# SINTETIZADOR_Y_DDS_SLAVE.net
KiCad netlist of a schematic drawn in Altium Designer
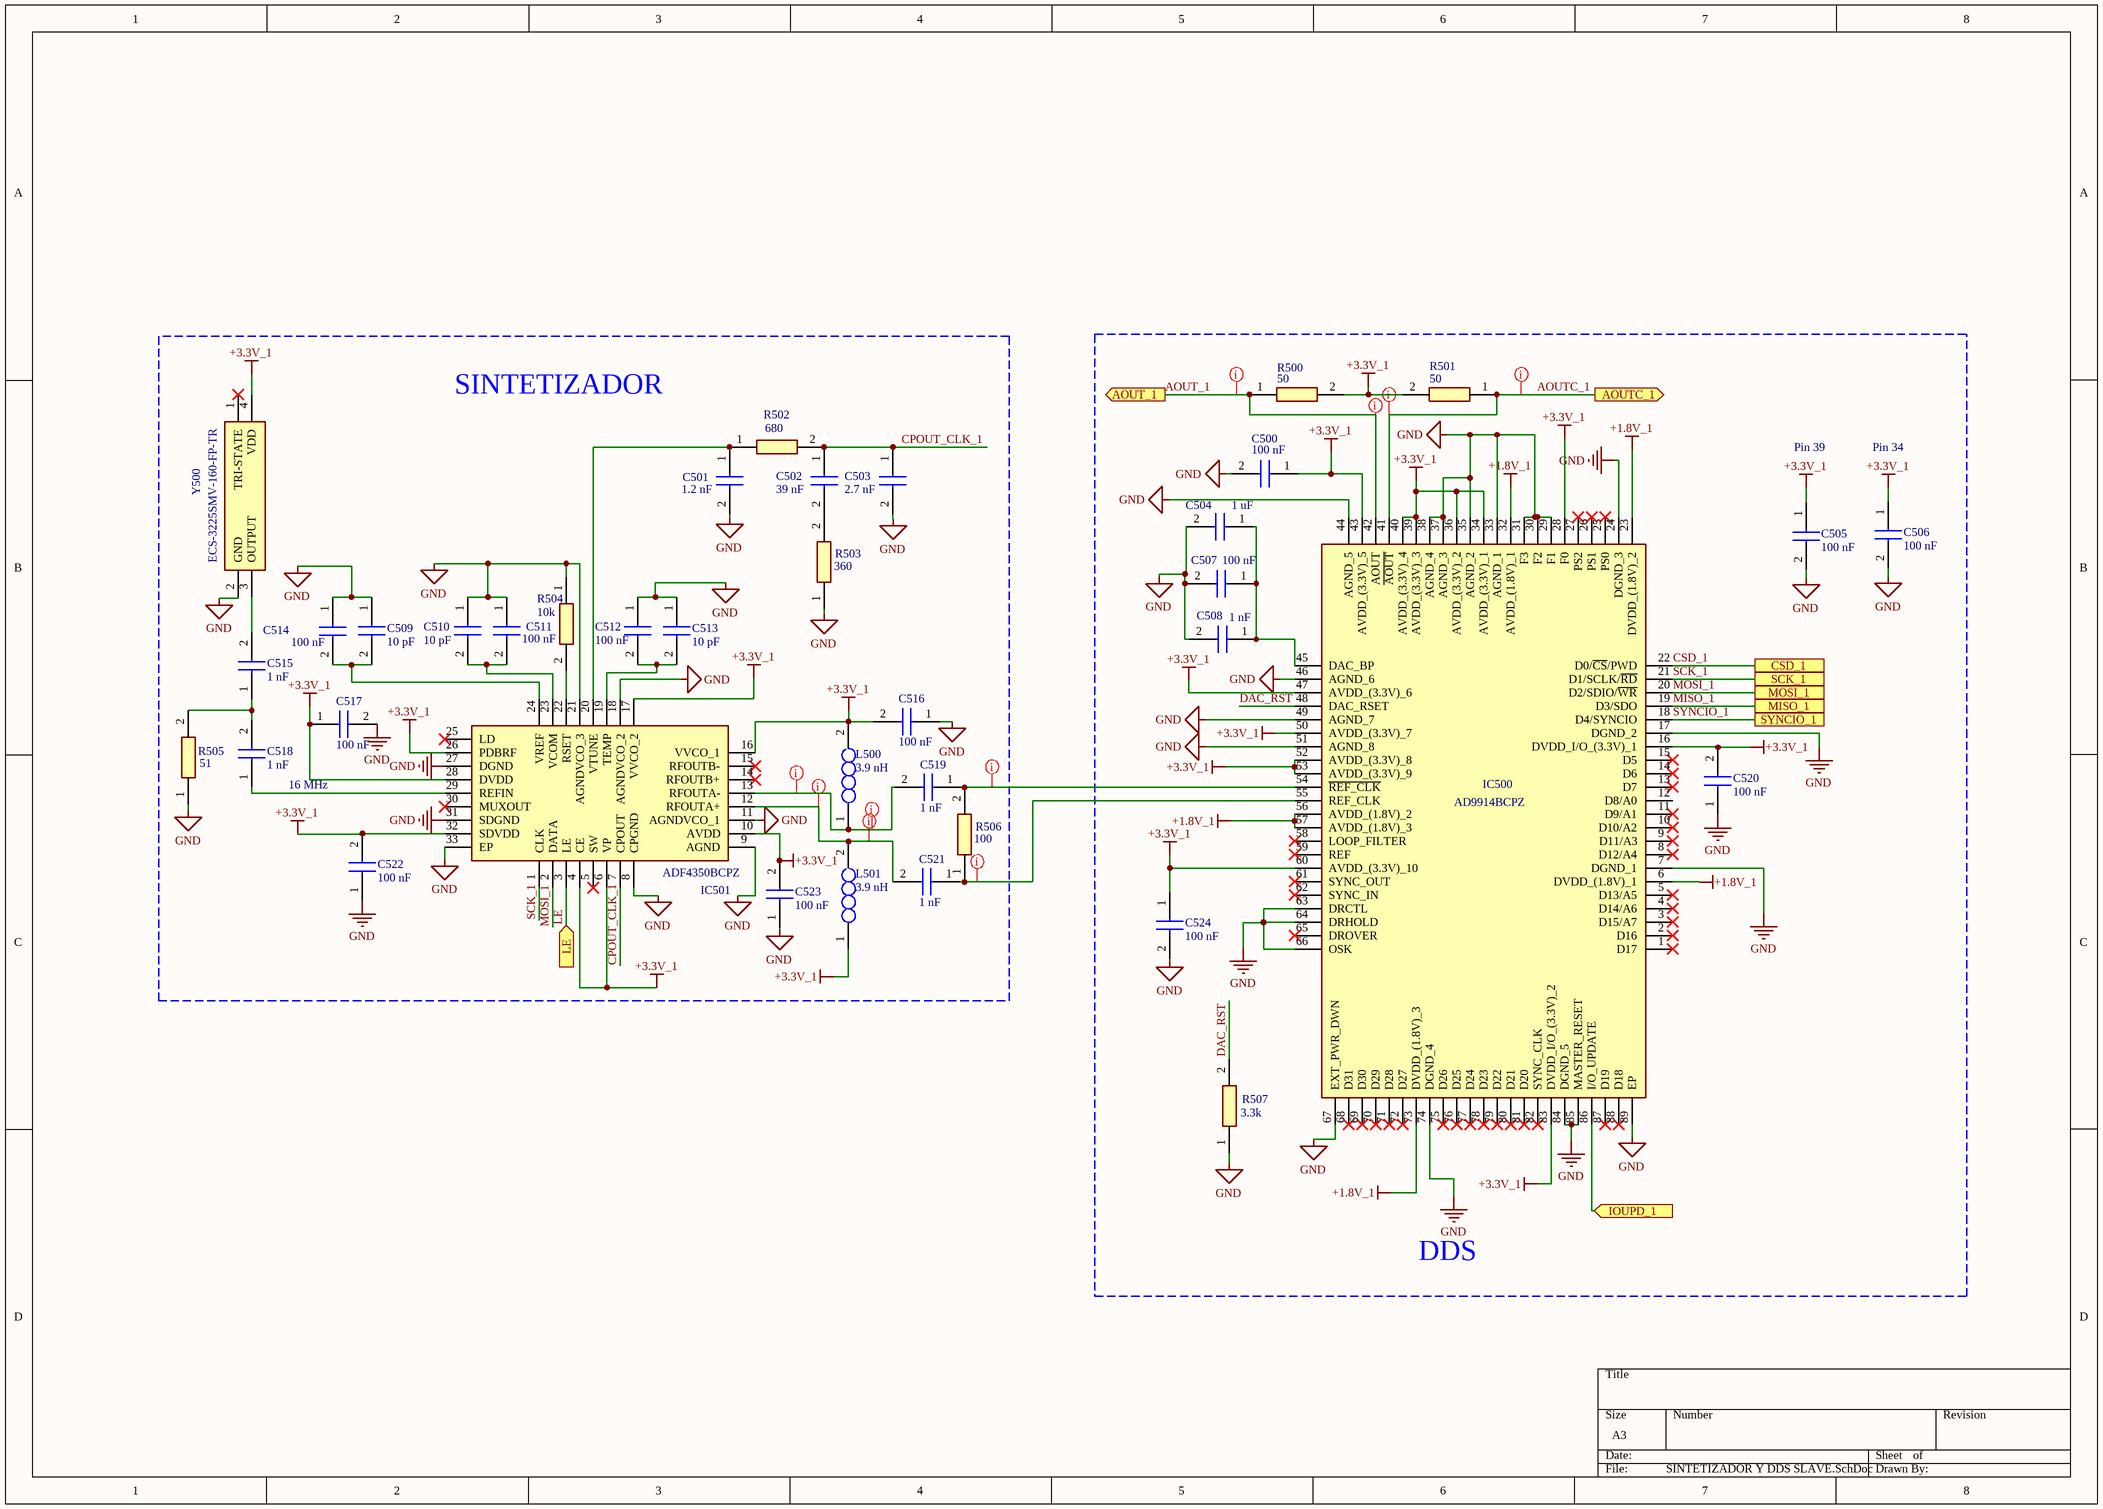
[diagram p0: SINTETIZADOR Y DDS SLAVE.SchDoc]

(export (version "E")
  (design (tool "Eeschema 10.0.6"))
  (components
    (comp (ref "C500")
      (value "100 nF")
      (footprint "SamacSys:C0603")
      (description "Capacitor")
      (fields (field (name "MANUFACTURER_PART_NUMBER") "C0603H470J5GACTU"))
      (libsource (lib "LIBRERIA_GEN_V2.0") (part "C0603H470J5GACTU"))
    )
    (comp (ref "C501")
      (value "1.2 nF")
      (footprint "SamacSys:C0603")
      (description "Capacitor")
      (fields (field (name "MANUFACTURER_PART_NUMBER") "C0603H470J5GACTU"))
      (libsource (lib "LIBRERIA_GEN_V2.0") (part "C0603H470J5GACTU"))
    )
    (comp (ref "C502")
      (value "39 nF")
      (footprint "SamacSys:C0603")
      (description "Capacitor")
      (fields (field (name "MANUFACTURER_PART_NUMBER") "C0603H470J5GACTU"))
      (libsource (lib "LIBRERIA_GEN_V2.0") (part "C0603H470J5GACTU"))
    )
    (comp (ref "C503")
      (value "2.7 nF")
      (footprint "SamacSys:C0603")
      (description "Capacitor")
      (fields (field (name "MANUFACTURER_PART_NUMBER") "C0603H470J5GACTU"))
      (libsource (lib "LIBRERIA_GEN_V2.0") (part "C0603H470J5GACTU"))
    )
    (comp (ref "C504")
      (value "1 uF")
      (footprint "SamacSys:C0603")
      (description "Capacitor")
      (fields (field (name "MANUFACTURER_PART_NUMBER") "C0603H470J5GACTU"))
      (libsource (lib "LIBRERIA_GEN_V2.0") (part "C0603H470J5GACTU"))
    )
    (comp (ref "C505")
      (value "100 nF")
      (footprint "SamacSys:C0603")
      (description "Capacitor")
      (fields (field (name "MANUFACTURER_PART_NUMBER") "C0603H470J5GACTU"))
      (libsource (lib "LIBRERIA_GEN_V2.0") (part "C0603H470J5GACTU"))
    )
    (comp (ref "C506")
      (value "100 nF")
      (footprint "SamacSys:C0603")
      (description "Capacitor")
      (fields (field (name "MANUFACTURER_PART_NUMBER") "C0603H470J5GACTU"))
      (libsource (lib "LIBRERIA_GEN_V2.0") (part "C0603H470J5GACTU"))
    )
    (comp (ref "C507")
      (value "100 nF")
      (footprint "SamacSys:C0603")
      (description "Capacitor")
      (fields (field (name "MANUFACTURER_PART_NUMBER") "C0603H470J5GACTU"))
      (libsource (lib "LIBRERIA_GEN_V2.0") (part "C0603H470J5GACTU"))
    )
    (comp (ref "C508")
      (value "1 nF")
      (footprint "SamacSys:C0603")
      (description "Capacitor")
      (fields (field (name "MANUFACTURER_PART_NUMBER") "C0603H470J5GACTU"))
      (libsource (lib "LIBRERIA_GEN_V2.0") (part "C0603H470J5GACTU"))
    )
    (comp (ref "C509")
      (value "10 pF")
      (footprint "SamacSys:C0603")
      (description "Capacitor")
      (fields (field (name "MANUFACTURER_PART_NUMBER") "C0603H470J5GACTU"))
      (libsource (lib "LIBRERIA_GEN_V2.0") (part "C0603H470J5GACTU"))
    )
    (comp (ref "C510")
      (value "10 pF")
      (footprint "SamacSys:C0603")
      (description "Capacitor")
      (fields (field (name "MANUFACTURER_PART_NUMBER") "C0603H470J5GACTU"))
      (libsource (lib "LIBRERIA_GEN_V2.0") (part "C0603H470J5GACTU"))
    )
    (comp (ref "C511")
      (value "100 nF")
      (footprint "SamacSys:C0603")
      (description "Capacitor")
      (fields (field (name "MANUFACTURER_PART_NUMBER") "C0603H470J5GACTU"))
      (libsource (lib "LIBRERIA_GEN_V2.0") (part "C0603H470J5GACTU"))
    )
    (comp (ref "C512")
      (value "100 nF")
      (footprint "SamacSys:C0603")
      (description "Capacitor")
      (fields (field (name "MANUFACTURER_PART_NUMBER") "C0603H470J5GACTU"))
      (libsource (lib "LIBRERIA_GEN_V2.0") (part "C0603H470J5GACTU"))
    )
    (comp (ref "C513")
      (value "10 pF")
      (footprint "SamacSys:C0603")
      (description "Capacitor")
      (fields (field (name "MANUFACTURER_PART_NUMBER") "C0603H470J5GACTU"))
      (libsource (lib "LIBRERIA_GEN_V2.0") (part "C0603H470J5GACTU"))
    )
    (comp (ref "C514")
      (value "100 nF")
      (footprint "SamacSys:C0603")
      (description "Capacitor")
      (fields (field (name "MANUFACTURER_PART_NUMBER") "C0603H470J5GACTU"))
      (libsource (lib "LIBRERIA_GEN_V2.0") (part "C0603H470J5GACTU"))
    )
    (comp (ref "C515")
      (value "1 nF")
      (footprint "SamacSys:C0603")
      (description "Capacitor")
      (fields (field (name "MANUFACTURER_PART_NUMBER") "C0603H470J5GACTU"))
      (libsource (lib "LIBRERIA_GEN_V2.0") (part "C0603H470J5GACTU"))
    )
    (comp (ref "C516")
      (value "100 nF")
      (footprint "SamacSys:C0603")
      (description "Capacitor")
      (fields (field (name "MANUFACTURER_PART_NUMBER") "C0603H470J5GACTU"))
      (libsource (lib "LIBRERIA_GEN_V2.0") (part "C0603H470J5GACTU"))
    )
    (comp (ref "C517")
      (value "100 nF")
      (footprint "SamacSys:C0603")
      (description "Capacitor")
      (fields (field (name "MANUFACTURER_PART_NUMBER") "C0603H470J5GACTU"))
      (libsource (lib "LIBRERIA_GEN_V2.0") (part "C0603H470J5GACTU"))
    )
    (comp (ref "C518")
      (value "1 nF")
      (footprint "SamacSys:C0603")
      (description "Capacitor")
      (fields (field (name "MANUFACTURER_PART_NUMBER") "C0603H470J5GACTU"))
      (libsource (lib "LIBRERIA_GEN_V2.0") (part "C0603H470J5GACTU"))
    )
    (comp (ref "C519")
      (value "1 nF")
      (footprint "SamacSys:C0603")
      (description "Capacitor")
      (fields (field (name "MANUFACTURER_PART_NUMBER") "C0603H470J5GACTU"))
      (libsource (lib "LIBRERIA_GEN_V2.0") (part "C0603H470J5GACTU"))
    )
    (comp (ref "C520")
      (value "100 nF")
      (footprint "SamacSys:C0603")
      (description "Capacitor")
      (fields (field (name "MANUFACTURER_PART_NUMBER") "C0603H470J5GACTU"))
      (libsource (lib "LIBRERIA_GEN_V2.0") (part "C0603H470J5GACTU"))
    )
    (comp (ref "C521")
      (value "1 nF")
      (footprint "SamacSys:C0603")
      (description "Capacitor")
      (fields (field (name "MANUFACTURER_PART_NUMBER") "C0603H470J5GACTU"))
      (libsource (lib "LIBRERIA_GEN_V2.0") (part "C0603H470J5GACTU"))
    )
    (comp (ref "C522")
      (value "100 nF")
      (footprint "SamacSys:C0603")
      (description "Capacitor")
      (fields (field (name "MANUFACTURER_PART_NUMBER") "C0603H470J5GACTU"))
      (libsource (lib "LIBRERIA_GEN_V2.0") (part "C0603H470J5GACTU"))
    )
    (comp (ref "C523")
      (value "100 nF")
      (footprint "SamacSys:C0603")
      (description "Capacitor")
      (fields (field (name "MANUFACTURER_PART_NUMBER") "C0603H470J5GACTU"))
      (libsource (lib "LIBRERIA_GEN_V2.0") (part "C0603H470J5GACTU"))
    )
    (comp (ref "C524")
      (value "100 nF")
      (footprint "SamacSys:C0603")
      (description "Capacitor")
      (fields (field (name "MANUFACTURER_PART_NUMBER") "C0603H470J5GACTU"))
      (libsource (lib "LIBRERIA_GEN_V2.0") (part "C0603H470J5GACTU"))
    )
    (comp (ref "IC500")
      (value "AD9914BCPZ")
      (footprint "SamacSys:QFN50P1200X1200X90-89N-D")
      (description "Integrated Circuit")
      (fields (field (name "MOUSER PART NUMBER") "584-AD9914BCPZ"))
      (libsource (lib "LIBRERIA_GEN_V2.0") (part "AD9914BCPZ"))
    )
    (comp (ref "IC501")
      (value "ADF4350BCPZ")
      (footprint "SamacSys:QFN50P500X500X100-33N")
      (description "Integrated Circuit")
      (fields (field (name "MOUSER PART NUMBER") "584-ADF4350BCPZ"))
      (libsource (lib "LIBRERIA_GEN_V2.0") (part "ADF4350BCPZ"))
    )
    (comp (ref "L500")
      (value "3.9 nH")
      (footprint "SamacSys:INDC1608X95N")
      (description "Inductor")
      (fields
        (field (name "MANUFACTURER_PART_NUMBER") "AIML-0603-100K-T")
        (field (name "MOUSER PART NUMBER") "815-AIML-0603-100KT")
      )
      (libsource (lib "*") (part "AIML-0603-100K-T"))
    )
    (comp (ref "L501")
      (value "3.9 nH")
      (footprint "SamacSys:INDC1608X95N")
      (description "Inductor")
      (fields
        (field (name "MANUFACTURER_PART_NUMBER") "AIML-0603-100K-T")
        (field (name "MOUSER PART NUMBER") "815-AIML-0603-100KT")
      )
      (libsource (lib "*") (part "AIML-0603-100K-T"))
    )
    (comp (ref "R500")
      (value "50")
      (footprint "SamacSys:RESC1608X55N")
      (description "Resistor")
      (fields
        (field (name "MANUFACTURER_PART_NUMBER") "CR0603-FX-1431ELF")
        (field (name "MOUSER PART NUMBER") "652-CR0603FX-1431ELF")
      )
      (libsource (lib "") (part "CR0603-FX-1431ELF_1"))
    )
    (comp (ref "R501")
      (value "50")
      (footprint "SamacSys:RESC1608X55N")
      (description "Resistor")
      (fields
        (field (name "MANUFACTURER_PART_NUMBER") "CR0603-FX-1431ELF")
        (field (name "MOUSER PART NUMBER") "652-CR0603FX-1431ELF")
      )
      (libsource (lib "") (part "CR0603-FX-1431ELF_3"))
    )
    (comp (ref "R502")
      (value "680")
      (footprint "SamacSys:RESC1608X55N")
      (description "Resistor")
      (fields
        (field (name "MANUFACTURER_PART_NUMBER") "CR0603-FX-1431ELF")
        (field (name "MOUSER PART NUMBER") "652-CR0603FX-1431ELF")
      )
      (libsource (lib "") (part "CR0603-FX-1431ELF_1"))
    )
    (comp (ref "R503")
      (value "360")
      (footprint "SamacSys:RESC1608X55N")
      (description "Resistor")
      (fields
        (field (name "MANUFACTURER_PART_NUMBER") "CR0603-FX-1431ELF")
        (field (name "MOUSER PART NUMBER") "652-CR0603FX-1431ELF")
      )
      (libsource (lib "") (part "CR0603-FX-1431ELF_2"))
    )
    (comp (ref "R504")
      (value "10k")
      (footprint "SamacSys:RESC1608X55N")
      (description "Resistor")
      (fields
        (field (name "MANUFACTURER_PART_NUMBER") "CR0603-FX-1431ELF")
        (field (name "MOUSER PART NUMBER") "652-CR0603FX-1431ELF")
      )
      (libsource (lib "LIBRERIA_GEN_V2.0") (part "CR0603-FX-1431ELF"))
    )
    (comp (ref "R505")
      (value "51")
      (footprint "SamacSys:RESC1608X55N")
      (description "Resistor")
      (fields
        (field (name "MANUFACTURER_PART_NUMBER") "CR0603-FX-1431ELF")
        (field (name "MOUSER PART NUMBER") "652-CR0603FX-1431ELF")
      )
      (libsource (lib "") (part "CR0603-FX-1431ELF_2"))
    )
    (comp (ref "R506")
      (value "100")
      (footprint "SamacSys:RESC1608X55N")
      (description "Resistor")
      (fields
        (field (name "MANUFACTURER_PART_NUMBER") "CR0603-FX-1431ELF")
        (field (name "MOUSER PART NUMBER") "652-CR0603FX-1431ELF")
      )
      (libsource (lib "") (part "CR0603-FX-1431ELF_2"))
    )
    (comp (ref "R507")
      (value "3.3k")
      (footprint "SamacSys:RESC1608X55N")
      (description "Resistor")
      (fields
        (field (name "MANUFACTURER_PART_NUMBER") "CR0603-FX-1431ELF")
        (field (name "MOUSER PART NUMBER") "652-CR0603FX-1431ELF")
      )
      (libsource (lib "") (part "CR0603-FX-1431ELF_2"))
    )
    (comp (ref "Y500")
      (value "ECS-3225SMV-160-FP-TR")
      (footprint "SamacSys:ECS3225SMV160FPTR")
      (description "Crystal or Oscillator")
      (fields (field (name "MOUSER PART NUMBER") "520-3225SMV-160-FPT"))
      (libsource (lib "LIBRERIA_GEN_V2.0") (part "ECS-3225SMV-160-FP-TR"))
    )
  )
  (nets
    (net (code "1") (name "+1.8V_1") (class "Default")
      (node (ref "IC500") (pin "23") (pinfunction "DVDD_(1.8V)_2_23") (pintype "passive"))
      (node (ref "IC500") (pin "32") (pinfunction "AVDD_(1.8V)_1_32") (pintype "passive"))
      (node (ref "IC500") (pin "56") (pinfunction "AVDD_(1.8V)_2_56") (pintype "passive"))
      (node (ref "IC500") (pin "57") (pinfunction "AVDD_(1.8V)_3_57") (pintype "passive"))
      (node (ref "IC500") (pin "6") (pinfunction "DVDD_(1.8V)_1_6") (pintype "passive"))
      (node (ref "IC500") (pin "73") (pinfunction "DVDD_(1.8V)_3_73") (pintype "passive"))
    )
    (net (code "2") (name "+3.3V_1") (class "Default")
      (node (ref "C500") (pin "1") (pinfunction "1_1") (pintype "passive"))
      (node (ref "C505") (pin "1") (pinfunction "1_1") (pintype "passive"))
      (node (ref "C506") (pin "1") (pinfunction "1_1") (pintype "passive"))
      (node (ref "C516") (pin "2") (pinfunction "2_2") (pintype "passive"))
      (node (ref "C517") (pin "1") (pinfunction "1_1") (pintype "passive"))
      (node (ref "C520") (pin "2") (pinfunction "2_2") (pintype "passive"))
      (node (ref "C522") (pin "2") (pinfunction "2_2") (pintype "passive"))
      (node (ref "C523") (pin "2") (pinfunction "2_2") (pintype "passive"))
      (node (ref "C524") (pin "1") (pinfunction "1_1") (pintype "passive"))
      (node (ref "IC500") (pin "16") (pinfunction "DVDD_I/O_(3.3V)_1_16") (pintype "passive"))
      (node (ref "IC500") (pin "28") (pinfunction "F0_28") (pintype "passive"))
      (node (ref "IC500") (pin "34") (pinfunction "AVDD_(3.3V)_1_34") (pintype "passive"))
      (node (ref "IC500") (pin "36") (pinfunction "AVDD_(3.3V)_2_36") (pintype "passive"))
      (node (ref "IC500") (pin "39") (pinfunction "AVDD_(3.3V)_3_39") (pintype "passive"))
      (node (ref "IC500") (pin "40") (pinfunction "AVDD_(3.3V)_4_40") (pintype "passive"))
      (node (ref "IC500") (pin "43") (pinfunction "AVDD_(3.3V)_5_43") (pintype "passive"))
      (node (ref "IC500") (pin "47") (pinfunction "AVDD_(3.3V)_6_47") (pintype "passive"))
      (node (ref "IC500") (pin "50") (pinfunction "AVDD_(3.3V)_7_50") (pintype "passive"))
      (node (ref "IC500") (pin "52") (pinfunction "AVDD_(3.3V)_8_52") (pintype "passive"))
      (node (ref "IC500") (pin "53") (pinfunction "AVDD_(3.3V)_9_53") (pintype "passive"))
      (node (ref "IC500") (pin "60") (pinfunction "AVDD_(3.3V)_10_60") (pintype "passive"))
      (node (ref "IC500") (pin "83") (pinfunction "DVDD_I/O_(3.3V)_2_83") (pintype "passive"))
      (node (ref "IC501") (pin "10") (pinfunction "AVDD_10") (pintype "passive"))
      (node (ref "IC501") (pin "16") (pinfunction "VVCO_1_16") (pintype "passive"))
      (node (ref "IC501") (pin "17") (pinfunction "VVCO_2_17") (pintype "passive"))
      (node (ref "IC501") (pin "26") (pinfunction "PDBRF_26") (pintype "passive"))
      (node (ref "IC501") (pin "28") (pinfunction "DVDD_28") (pintype "passive"))
      (node (ref "IC501") (pin "32") (pinfunction "SDVDD_32") (pintype "passive"))
      (node (ref "IC501") (pin "4") (pinfunction "CE_4") (pintype "passive"))
      (node (ref "IC501") (pin "6") (pinfunction "VP_6") (pintype "passive"))
      (node (ref "L500") (pin "2") (pinfunction "2_2") (pintype "passive"))
      (node (ref "L501") (pin "1") (pinfunction "1_1") (pintype "passive"))
      (node (ref "R500") (pin "2") (pinfunction "2_2") (pintype "passive"))
      (node (ref "R501") (pin "2") (pinfunction "2_2") (pintype "passive"))
      (node (ref "Y500") (pin "4") (pinfunction "VDD_4") (pintype "passive"))
    )
    (net (code "3") (name "/AOUTC_1") (class "Default")
      (node (ref "IC500") (pin "41") (pinfunction "~{AOUT}_41") (pintype "passive"))
      (node (ref "R501") (pin "1") (pinfunction "1_1") (pintype "passive"))
    )
    (net (code "4") (name "/AOUT_1") (class "Default")
      (node (ref "IC500") (pin "42") (pinfunction "AOUT_42") (pintype "passive"))
      (node (ref "R500") (pin "1") (pinfunction "1_1") (pintype "passive"))
    )
    (net (code "5") (name "/CPOUT_CLK_1") (class "Default")
      (node (ref "C502") (pin "1") (pinfunction "1_1") (pintype "passive"))
      (node (ref "C503") (pin "1") (pinfunction "1_1") (pintype "passive"))
      (node (ref "IC501") (pin "7") (pinfunction "CPOUT_7") (pintype "passive"))
      (node (ref "R502") (pin "2") (pinfunction "2_2") (pintype "passive"))
    )
    (net (code "6") (name "/CSD_1") (class "Default")
      (node (ref "IC500") (pin "22") (pinfunction "D0/~{CS}/PWD_22") (pintype "passive"))
    )
    (net (code "7") (name "/DAC_RST") (class "Default")
      (node (ref "IC500") (pin "48") (pinfunction "DAC_RSET_48") (pintype "passive"))
      (node (ref "R507") (pin "2") (pinfunction "2_2") (pintype "passive"))
    )
    (net (code "8") (name "/IOUPD_1") (class "Default")
      (node (ref "IC500") (pin "86") (pinfunction "I/O_UPDATE_86") (pintype "passive"))
    )
    (net (code "9") (name "/LE") (class "Default")
      (node (ref "IC501") (pin "3") (pinfunction "LE_3") (pintype "passive"))
    )
    (net (code "10") (name "/MISO_1") (class "Default")
      (node (ref "IC500") (pin "19") (pinfunction "D3/SDO_19") (pintype "passive"))
    )
    (net (code "11") (name "/MOSI_1") (class "Default")
      (node (ref "IC500") (pin "20") (pinfunction "D2/SDIO/~{WR}_20") (pintype "passive"))
      (node (ref "IC501") (pin "2") (pinfunction "DATA_2") (pintype "passive"))
    )
    (net (code "12") (name "/SCK_1") (class "Default")
      (node (ref "IC500") (pin "21") (pinfunction "D1/SCLK/~{RD}_21") (pintype "passive"))
      (node (ref "IC501") (pin "1") (pinfunction "CLK_1") (pintype "passive"))
    )
    (net (code "13") (name "/SYNCIO_1") (class "Default")
      (node (ref "IC500") (pin "18") (pinfunction "D4/SYNCIO_18") (pintype "passive"))
    )
    (net (code "14") (name "GND") (class "Default")
      (node (ref "C500") (pin "2") (pinfunction "2_2") (pintype "passive"))
      (node (ref "C501") (pin "2") (pinfunction "2_2") (pintype "passive"))
      (node (ref "C503") (pin "2") (pinfunction "2_2") (pintype "passive"))
      (node (ref "C504") (pin "2") (pinfunction "2_2") (pintype "passive"))
      (node (ref "C505") (pin "2") (pinfunction "2_2") (pintype "passive"))
      (node (ref "C506") (pin "2") (pinfunction "2_2") (pintype "passive"))
      (node (ref "C507") (pin "2") (pinfunction "2_2") (pintype "passive"))
      (node (ref "C508") (pin "2") (pinfunction "2_2") (pintype "passive"))
      (node (ref "C509") (pin "1") (pinfunction "1_1") (pintype "passive"))
      (node (ref "C510") (pin "1") (pinfunction "1_1") (pintype "passive"))
      (node (ref "C511") (pin "1") (pinfunction "1_1") (pintype "passive"))
      (node (ref "C512") (pin "1") (pinfunction "1_1") (pintype "passive"))
      (node (ref "C513") (pin "1") (pinfunction "1_1") (pintype "passive"))
      (node (ref "C514") (pin "1") (pinfunction "1_1") (pintype "passive"))
      (node (ref "C516") (pin "1") (pinfunction "1_1") (pintype "passive"))
      (node (ref "C517") (pin "2") (pinfunction "2_2") (pintype "passive"))
      (node (ref "C520") (pin "1") (pinfunction "1_1") (pintype "passive"))
      (node (ref "C522") (pin "1") (pinfunction "1_1") (pintype "passive"))
      (node (ref "C523") (pin "1") (pinfunction "1_1") (pintype "passive"))
      (node (ref "C524") (pin "2") (pinfunction "2_2") (pintype "passive"))
      (node (ref "IC500") (pin "17") (pinfunction "DGND_2_17") (pintype "passive"))
      (node (ref "IC500") (pin "24") (pinfunction "DGND_3_24") (pintype "passive"))
      (node (ref "IC500") (pin "29") (pinfunction "F1_29") (pintype "passive"))
      (node (ref "IC500") (pin "30") (pinfunction "F2_30") (pintype "passive"))
      (node (ref "IC500") (pin "31") (pinfunction "F3_31") (pintype "passive"))
      (node (ref "IC500") (pin "33") (pinfunction "AGND_1_33") (pintype "passive"))
      (node (ref "IC500") (pin "35") (pinfunction "AGND_2_35") (pintype "passive"))
      (node (ref "IC500") (pin "37") (pinfunction "AGND_3_37") (pintype "passive"))
      (node (ref "IC500") (pin "38") (pinfunction "AGND_4_38") (pintype "passive"))
      (node (ref "IC500") (pin "44") (pinfunction "AGND_5_44") (pintype "passive"))
      (node (ref "IC500") (pin "46") (pinfunction "AGND_6_46") (pintype "passive"))
      (node (ref "IC500") (pin "49") (pinfunction "AGND_7_49") (pintype "passive"))
      (node (ref "IC500") (pin "51") (pinfunction "AGND_8_51") (pintype "passive"))
      (node (ref "IC500") (pin "63") (pinfunction "DRCTL_63") (pintype "passive"))
      (node (ref "IC500") (pin "64") (pinfunction "DRHOLD_64") (pintype "passive"))
      (node (ref "IC500") (pin "66") (pinfunction "OSK_66") (pintype "passive"))
      (node (ref "IC500") (pin "67") (pinfunction "EXT_PWR_DWN_67") (pintype "passive"))
      (node (ref "IC500") (pin "7") (pinfunction "DGND_1_7") (pintype "passive"))
      (node (ref "IC500") (pin "74") (pinfunction "DGND_4_74") (pintype "passive"))
      (node (ref "IC500") (pin "84") (pinfunction "DGND_5_84") (pintype "passive"))
      (node (ref "IC500") (pin "85") (pinfunction "MASTER_RESET_85") (pintype "passive"))
      (node (ref "IC500") (pin "89") (pinfunction "EP_89") (pintype "passive"))
      (node (ref "IC501") (pin "11") (pinfunction "AGNDVCO_1_11") (pintype "passive"))
      (node (ref "IC501") (pin "18") (pinfunction "AGNDVCO_2_18") (pintype "passive"))
      (node (ref "IC501") (pin "21") (pinfunction "AGNDVCO_3_21") (pintype "passive"))
      (node (ref "IC501") (pin "27") (pinfunction "DGND_27") (pintype "passive"))
      (node (ref "IC501") (pin "31") (pinfunction "SDGND_31") (pintype "passive"))
      (node (ref "IC501") (pin "33") (pinfunction "EP_33") (pintype "passive"))
      (node (ref "IC501") (pin "8") (pinfunction "CPGND_8") (pintype "passive"))
      (node (ref "IC501") (pin "9") (pinfunction "AGND_9") (pintype "passive"))
      (node (ref "R503") (pin "1") (pinfunction "1_1") (pintype "passive"))
      (node (ref "R504") (pin "1") (pinfunction "1_1") (pintype "passive"))
      (node (ref "R505") (pin "1") (pinfunction "1_1") (pintype "passive"))
      (node (ref "R507") (pin "1") (pinfunction "1_1") (pintype "passive"))
      (node (ref "Y500") (pin "2") (pinfunction "GND_2") (pintype "passive"))
    )
    (net (code "15") (name "Net-(C502-Pad2)") (class "Default")
      (node (ref "C502") (pin "2") (pinfunction "2_2") (pintype "passive"))
      (node (ref "R503") (pin "2") (pinfunction "2_2") (pintype "passive"))
    )
    (net (code "16") (name "Net-(C515-Pad1)") (class "Default")
      (node (ref "C515") (pin "1") (pinfunction "1_1") (pintype "passive"))
      (node (ref "C518") (pin "2") (pinfunction "2_2") (pintype "passive"))
      (node (ref "R505") (pin "2") (pinfunction "2_2") (pintype "passive"))
    )
    (net (code "17") (name "Net-(IC500-DAC_BP)") (class "Default")
      (node (ref "C504") (pin "1") (pinfunction "1_1") (pintype "passive"))
      (node (ref "C507") (pin "1") (pinfunction "1_1") (pintype "passive"))
      (node (ref "C508") (pin "1") (pinfunction "1_1") (pintype "passive"))
      (node (ref "IC500") (pin "45") (pinfunction "DAC_BP_45") (pintype "passive"))
    )
    (net (code "18") (name "Net-(IC500-REF_CLK)") (class "Default")
      (node (ref "C521") (pin "1") (pinfunction "1_1") (pintype "passive"))
      (node (ref "IC500") (pin "55") (pinfunction "REF_CLK_55") (pintype "passive"))
      (node (ref "R506") (pin "1") (pinfunction "1_1") (pintype "passive"))
    )
    (net (code "19") (name "Net-(IC500-~{REF_CLK})") (class "Default")
      (node (ref "C519") (pin "1") (pinfunction "1_1") (pintype "passive"))
      (node (ref "IC500") (pin "54") (pinfunction "~{REF_CLK}_54") (pintype "passive"))
      (node (ref "R506") (pin "2") (pinfunction "2_2") (pintype "passive"))
    )
    (net (code "20") (name "Net-(IC501-REFIN)") (class "Default")
      (node (ref "C518") (pin "1") (pinfunction "1_1") (pintype "passive"))
      (node (ref "IC501") (pin "29") (pinfunction "REFIN_29") (pintype "passive"))
    )
    (net (code "21") (name "Net-(IC501-RFOUTA+)") (class "Default")
      (node (ref "C521") (pin "2") (pinfunction "2_2") (pintype "passive"))
      (node (ref "IC501") (pin "12") (pinfunction "RFOUTA+_12") (pintype "passive"))
      (node (ref "L501") (pin "2") (pinfunction "2_2") (pintype "passive"))
    )
    (net (code "22") (name "Net-(IC501-RFOUTA-)") (class "Default")
      (node (ref "C519") (pin "2") (pinfunction "2_2") (pintype "passive"))
      (node (ref "IC501") (pin "13") (pinfunction "RFOUTA-_13") (pintype "passive"))
      (node (ref "L500") (pin "1") (pinfunction "1_1") (pintype "passive"))
    )
    (net (code "23") (name "Net-(IC501-RSET)") (class "Default")
      (node (ref "IC501") (pin "22") (pinfunction "RSET_22") (pintype "passive"))
      (node (ref "R504") (pin "2") (pinfunction "2_2") (pintype "passive"))
    )
    (net (code "24") (name "Net-(IC501-TEMP)") (class "Default")
      (node (ref "C512") (pin "2") (pinfunction "2_2") (pintype "passive"))
      (node (ref "C513") (pin "2") (pinfunction "2_2") (pintype "passive"))
      (node (ref "IC501") (pin "19") (pinfunction "TEMP_19") (pintype "passive"))
    )
    (net (code "25") (name "Net-(IC501-VCOM)") (class "Default")
      (node (ref "C510") (pin "2") (pinfunction "2_2") (pintype "passive"))
      (node (ref "C511") (pin "2") (pinfunction "2_2") (pintype "passive"))
      (node (ref "IC501") (pin "23") (pinfunction "VCOM_23") (pintype "passive"))
    )
    (net (code "26") (name "Net-(IC501-VREF)") (class "Default")
      (node (ref "C509") (pin "2") (pinfunction "2_2") (pintype "passive"))
      (node (ref "C514") (pin "2") (pinfunction "2_2") (pintype "passive"))
      (node (ref "IC501") (pin "24") (pinfunction "VREF_24") (pintype "passive"))
    )
    (net (code "27") (name "Net-(IC501-VTUNE)") (class "Default")
      (node (ref "C501") (pin "1") (pinfunction "1_1") (pintype "passive"))
      (node (ref "IC501") (pin "20") (pinfunction "VTUNE_20") (pintype "passive"))
      (node (ref "R502") (pin "1") (pinfunction "1_1") (pintype "passive"))
    )
    (net (code "28") (name "Net-(Y500-OUTPUT)") (class "Default")
      (node (ref "C515") (pin "2") (pinfunction "2_2") (pintype "passive"))
      (node (ref "Y500") (pin "3") (pinfunction "OUTPUT_3") (pintype "passive"))
    )
    (net (code "29") (name "unconnected-(IC500-D5-Pad15)") (class "Default")
      (node (ref "IC500") (pin "15") (pinfunction "D5_15") (pintype "passive+no_connect"))
    )
    (net (code "30") (name "unconnected-(IC500-D6-Pad14)") (class "Default")
      (node (ref "IC500") (pin "14") (pinfunction "D6_14") (pintype "passive+no_connect"))
    )
    (net (code "31") (name "unconnected-(IC500-D7-Pad13)") (class "Default")
      (node (ref "IC500") (pin "13") (pinfunction "D7_13") (pintype "passive+no_connect"))
    )
    (net (code "32") (name "unconnected-(IC500-D8{slash}A0-Pad12)") (class "Default")
      (node (ref "IC500") (pin "12") (pinfunction "D8/A0_12") (pintype "passive"))
    )
    (net (code "33") (name "unconnected-(IC500-D9{slash}A1-Pad11)") (class "Default")
      (node (ref "IC500") (pin "11") (pinfunction "D9/A1_11") (pintype "passive+no_connect"))
    )
    (net (code "34") (name "unconnected-(IC500-D10{slash}A2-Pad10)") (class "Default")
      (node (ref "IC500") (pin "10") (pinfunction "D10/A2_10") (pintype "passive+no_connect"))
    )
    (net (code "35") (name "unconnected-(IC500-D11{slash}A3-Pad9)") (class "Default")
      (node (ref "IC500") (pin "9") (pinfunction "D11/A3_9") (pintype "passive+no_connect"))
    )
    (net (code "36") (name "unconnected-(IC500-D12{slash}A4-Pad8)") (class "Default")
      (node (ref "IC500") (pin "8") (pinfunction "D12/A4_8") (pintype "passive+no_connect"))
    )
    (net (code "37") (name "unconnected-(IC500-D13{slash}A5-Pad5)") (class "Default")
      (node (ref "IC500") (pin "5") (pinfunction "D13/A5_5") (pintype "passive+no_connect"))
    )
    (net (code "38") (name "unconnected-(IC500-D14{slash}A6-Pad4)") (class "Default")
      (node (ref "IC500") (pin "4") (pinfunction "D14/A6_4") (pintype "passive+no_connect"))
    )
    (net (code "39") (name "unconnected-(IC500-D15{slash}A7-Pad3)") (class "Default")
      (node (ref "IC500") (pin "3") (pinfunction "D15/A7_3") (pintype "passive+no_connect"))
    )
    (net (code "40") (name "unconnected-(IC500-D16-Pad2)") (class "Default")
      (node (ref "IC500") (pin "2") (pinfunction "D16_2") (pintype "passive+no_connect"))
    )
    (net (code "41") (name "unconnected-(IC500-D17-Pad1)") (class "Default")
      (node (ref "IC500") (pin "1") (pinfunction "D17_1") (pintype "passive+no_connect"))
    )
    (net (code "42") (name "unconnected-(IC500-D18-Pad88)") (class "Default")
      (node (ref "IC500") (pin "88") (pinfunction "D18_88") (pintype "passive+no_connect"))
    )
    (net (code "43") (name "unconnected-(IC500-D19-Pad87)") (class "Default")
      (node (ref "IC500") (pin "87") (pinfunction "D19_87") (pintype "passive+no_connect"))
    )
    (net (code "44") (name "unconnected-(IC500-D20-Pad81)") (class "Default")
      (node (ref "IC500") (pin "81") (pinfunction "D20_81") (pintype "passive+no_connect"))
    )
    (net (code "45") (name "unconnected-(IC500-D21-Pad80)") (class "Default")
      (node (ref "IC500") (pin "80") (pinfunction "D21_80") (pintype "passive+no_connect"))
    )
    (net (code "46") (name "unconnected-(IC500-D22-Pad79)") (class "Default")
      (node (ref "IC500") (pin "79") (pinfunction "D22_79") (pintype "passive+no_connect"))
    )
    (net (code "47") (name "unconnected-(IC500-D23-Pad78)") (class "Default")
      (node (ref "IC500") (pin "78") (pinfunction "D23_78") (pintype "passive+no_connect"))
    )
    (net (code "48") (name "unconnected-(IC500-D24-Pad77)") (class "Default")
      (node (ref "IC500") (pin "77") (pinfunction "D24_77") (pintype "passive+no_connect"))
    )
    (net (code "49") (name "unconnected-(IC500-D25-Pad76)") (class "Default")
      (node (ref "IC500") (pin "76") (pinfunction "D25_76") (pintype "passive+no_connect"))
    )
    (net (code "50") (name "unconnected-(IC500-D26-Pad75)") (class "Default")
      (node (ref "IC500") (pin "75") (pinfunction "D26_75") (pintype "passive+no_connect"))
    )
    (net (code "51") (name "unconnected-(IC500-D27-Pad72)") (class "Default")
      (node (ref "IC500") (pin "72") (pinfunction "D27_72") (pintype "passive+no_connect"))
    )
    (net (code "52") (name "unconnected-(IC500-D28-Pad71)") (class "Default")
      (node (ref "IC500") (pin "71") (pinfunction "D28_71") (pintype "passive+no_connect"))
    )
    (net (code "53") (name "unconnected-(IC500-D29-Pad70)") (class "Default")
      (node (ref "IC500") (pin "70") (pinfunction "D29_70") (pintype "passive+no_connect"))
    )
    (net (code "54") (name "unconnected-(IC500-D30-Pad69)") (class "Default")
      (node (ref "IC500") (pin "69") (pinfunction "D30_69") (pintype "passive+no_connect"))
    )
    (net (code "55") (name "unconnected-(IC500-D31-Pad68)") (class "Default")
      (node (ref "IC500") (pin "68") (pinfunction "D31_68") (pintype "passive+no_connect"))
    )
    (net (code "56") (name "unconnected-(IC500-DROVER-Pad65)") (class "Default")
      (node (ref "IC500") (pin "65") (pinfunction "DROVER_65") (pintype "passive+no_connect"))
    )
    (net (code "57") (name "unconnected-(IC500-LOOP_FILTER-Pad58)") (class "Default")
      (node (ref "IC500") (pin "58") (pinfunction "LOOP_FILTER_58") (pintype "passive+no_connect"))
    )
    (net (code "58") (name "unconnected-(IC500-PS0-Pad25)") (class "Default")
      (node (ref "IC500") (pin "25") (pinfunction "PS0_25") (pintype "passive+no_connect"))
    )
    (net (code "59") (name "unconnected-(IC500-PS1-Pad26)") (class "Default")
      (node (ref "IC500") (pin "26") (pinfunction "PS1_26") (pintype "passive+no_connect"))
    )
    (net (code "60") (name "unconnected-(IC500-PS2-Pad27)") (class "Default")
      (node (ref "IC500") (pin "27") (pinfunction "PS2_27") (pintype "passive+no_connect"))
    )
    (net (code "61") (name "unconnected-(IC500-REF-Pad59)") (class "Default")
      (node (ref "IC500") (pin "59") (pinfunction "REF_59") (pintype "passive+no_connect"))
    )
    (net (code "62") (name "unconnected-(IC500-SYNC_CLK-Pad82)") (class "Default")
      (node (ref "IC500") (pin "82") (pinfunction "SYNC_CLK_82") (pintype "passive+no_connect"))
    )
    (net (code "63") (name "unconnected-(IC500-SYNC_IN-Pad62)") (class "Default")
      (node (ref "IC500") (pin "62") (pinfunction "SYNC_IN_62") (pintype "passive+no_connect"))
    )
    (net (code "64") (name "unconnected-(IC500-SYNC_OUT-Pad61)") (class "Default")
      (node (ref "IC500") (pin "61") (pinfunction "SYNC_OUT_61") (pintype "passive+no_connect"))
    )
    (net (code "65") (name "unconnected-(IC501-LD-Pad25)") (class "Default")
      (node (ref "IC501") (pin "25") (pinfunction "LD_25") (pintype "passive+no_connect"))
    )
    (net (code "66") (name "unconnected-(IC501-MUXOUT-Pad30)") (class "Default")
      (node (ref "IC501") (pin "30") (pinfunction "MUXOUT_30") (pintype "passive+no_connect"))
    )
    (net (code "67") (name "unconnected-(IC501-RFOUTB+-Pad14)") (class "Default")
      (node (ref "IC501") (pin "14") (pinfunction "RFOUTB+_14") (pintype "passive+no_connect"))
    )
    (net (code "68") (name "unconnected-(IC501-RFOUTB--Pad15)") (class "Default")
      (node (ref "IC501") (pin "15") (pinfunction "RFOUTB-_15") (pintype "passive+no_connect"))
    )
    (net (code "69") (name "unconnected-(IC501-SW-Pad5)") (class "Default")
      (node (ref "IC501") (pin "5") (pinfunction "SW_5") (pintype "passive+no_connect"))
    )
    (net (code "70") (name "unconnected-(Y500-TRI-STATE-Pad1)") (class "Default")
      (node (ref "Y500") (pin "1") (pinfunction "TRI-STATE_1") (pintype "passive+no_connect"))
    )
  )
)
